# MCU.net
KiCad netlist of a schematic drawn in Altium Designer
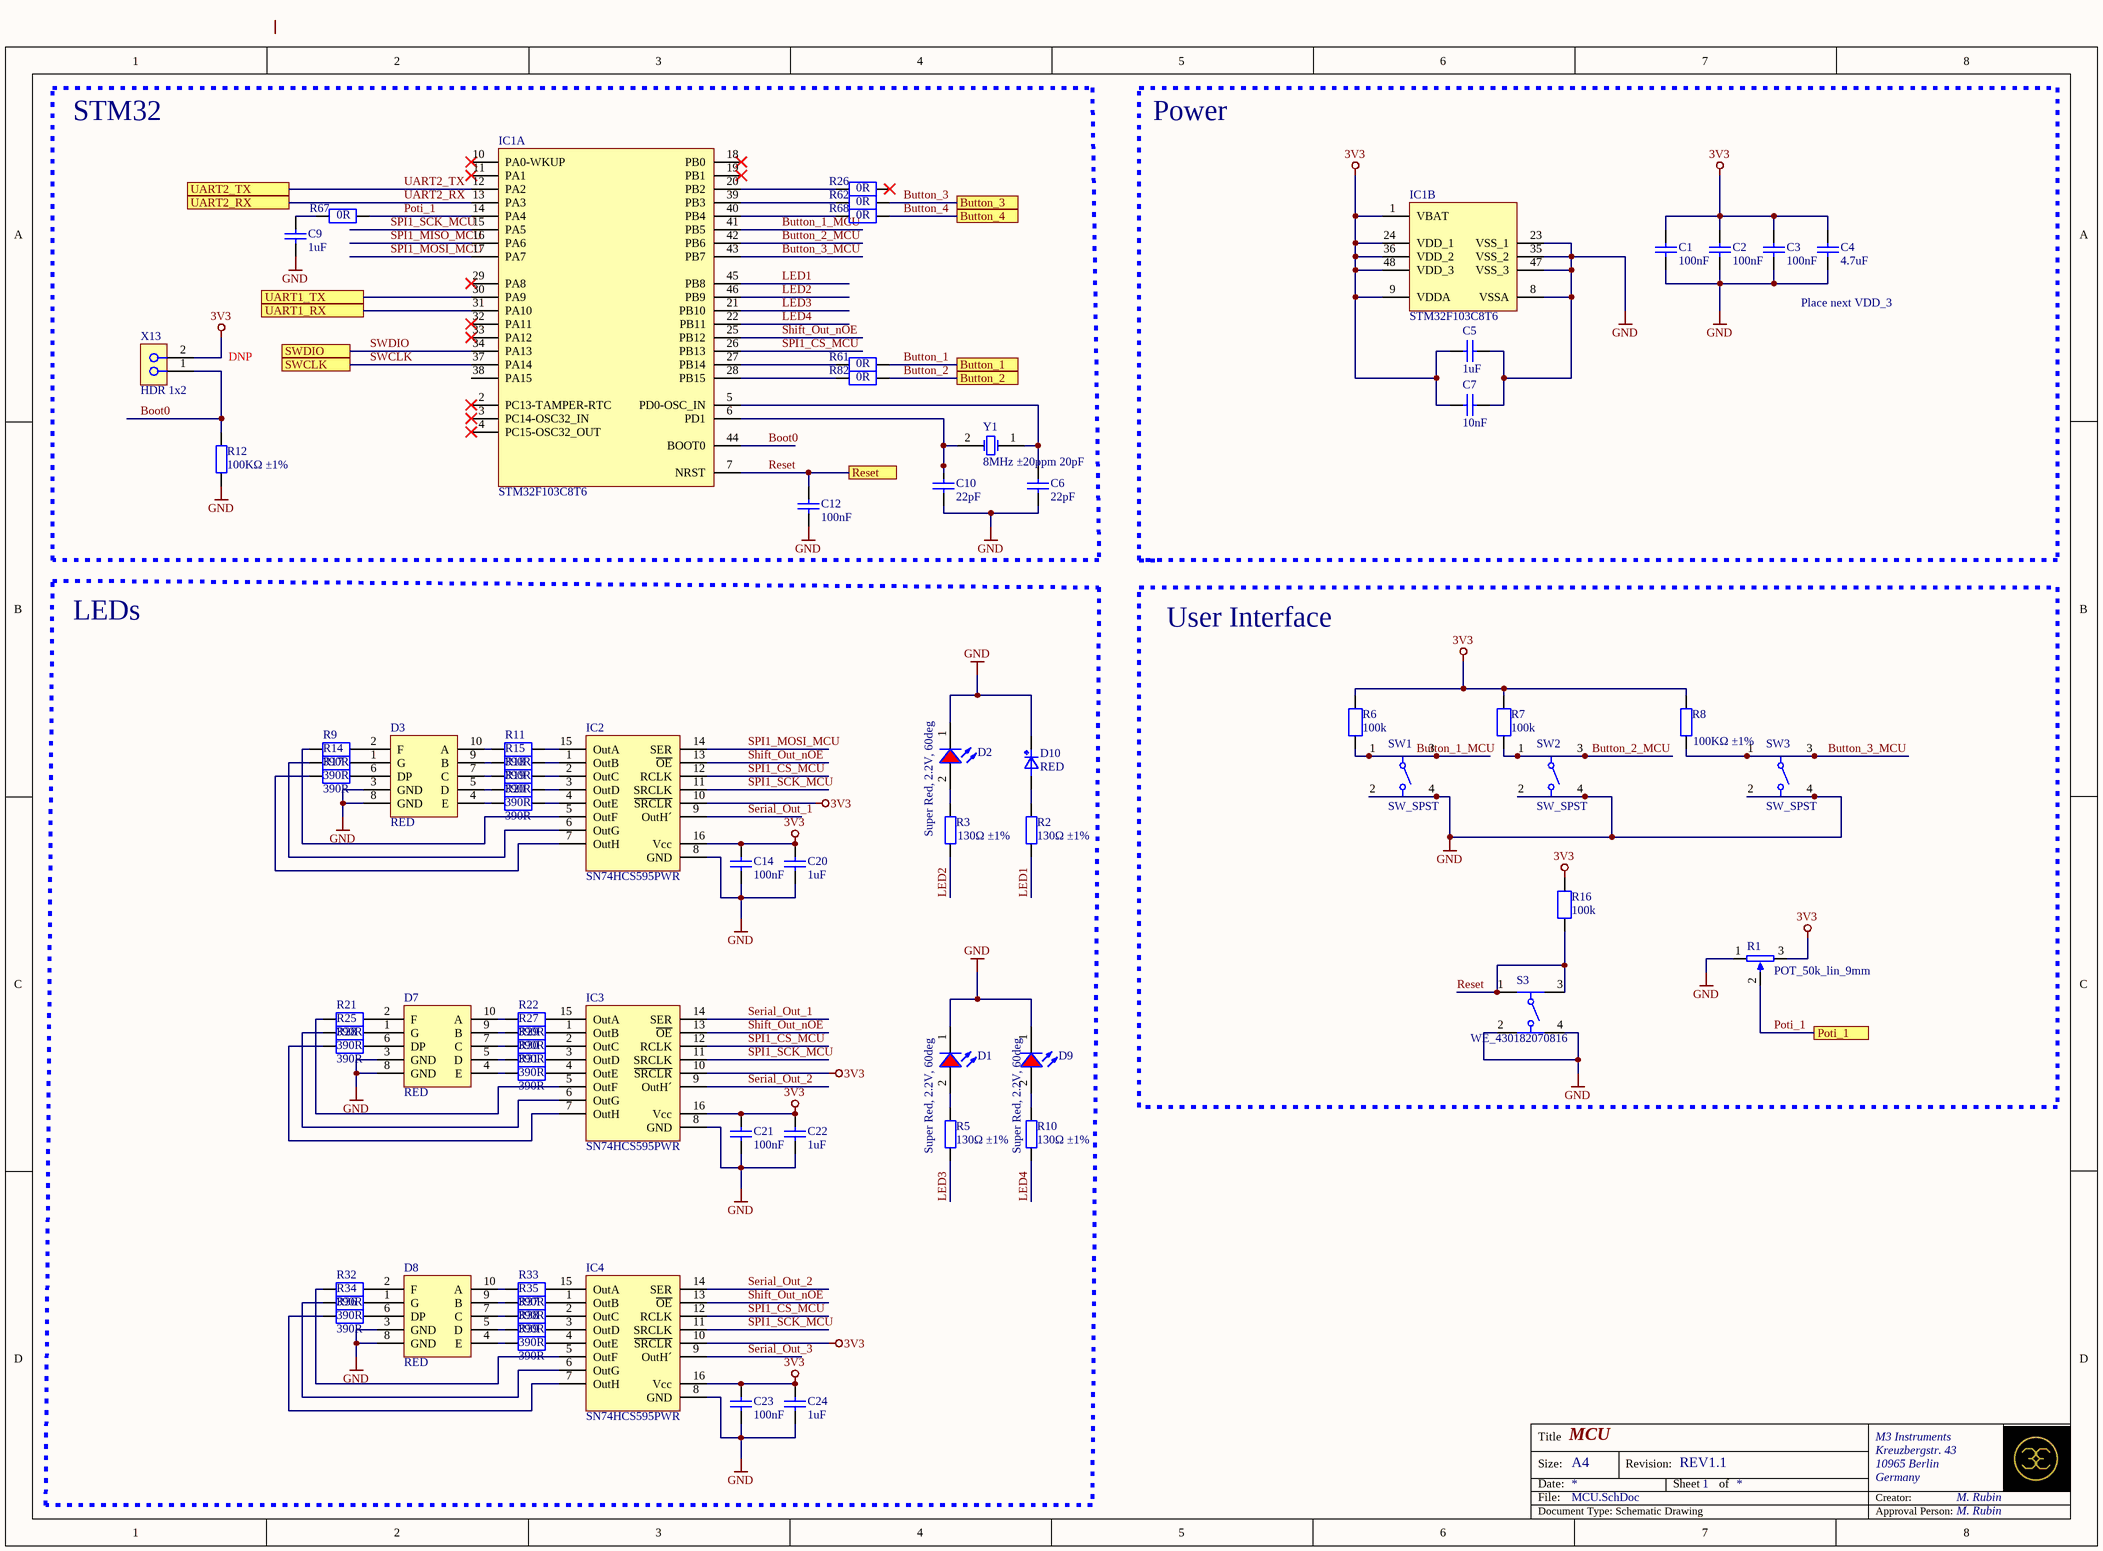
[diagram p0: MCU.SchDoc]

(export (version "E")
  (design (tool "Eeschema 10.0.6"))
  (components
    (comp (ref "C1")
      (value "100nF")
      (footprint "0603_C")
      (description "Chip capacitors")
      (fields (field (name "MANUFACTURER") "YAGEO") (field (name "PARTNUMBER") "CC0603KRX7R9BB104"))
      (libsource (lib "Cap") (part "0603 100nF (104) 10% 50V"))
    )
    (comp (ref "C2")
      (value "100nF")
      (footprint "0603_C")
      (description "Chip capacitors")
      (fields (field (name "MANUFACTURER") "YAGEO") (field (name "PARTNUMBER") "CC0603KRX7R9BB104"))
      (libsource (lib "Cap") (part "0603 100nF (104) 10% 50V"))
    )
    (comp (ref "C3")
      (value "100nF")
      (footprint "0603_C")
      (description "Chip capacitors")
      (fields (field (name "MANUFACTURER") "YAGEO") (field (name "PARTNUMBER") "CC0603KRX7R9BB104"))
      (libsource (lib "Cap") (part "0603 100nF (104) 10% 50V"))
    )
    (comp (ref "C4")
      (value "4.7uF")
      (footprint "0603_C")
      (description "Chip capacitors")
      (fields
        (field (name "MANUFACTURER") "Samsung Electro-Mechanics")
        (field (name "PARTNUMBER") "CL10A475KO8NNNC")
      )
      (libsource (lib "Cap") (part "0603 4.7uF (475) 10% 16V"))
    )
    (comp (ref "C5")
      (value "1uF")
      (footprint "0603_C")
      (description "Chip capacitors")
      (fields
        (field (name "MANUFACTURER") "Samsung Electro-Mechanics")
        (field (name "PARTNUMBER") "CL10A105KB8NNNC")
      )
      (libsource (lib "Cap") (part "0603 1uF (105) 10% 50V"))
    )
    (comp (ref "C6")
      (value "22pF")
      (footprint "0603_C")
      (description "Chip capacitors")
      (fields
        (field (name "MANUFACTURER") "Samsung Electro-Mechanics")
        (field (name "PARTNUMBER") "CL10C220JB8NNNC")
      )
      (libsource (lib "Cap") (part "0603 22pF (220) 5% 50V"))
    )
    (comp (ref "C7")
      (value "10nF")
      (footprint "0603_C")
      (description "Chip capacitors")
      (fields
        (field (name "MANUFACTURER") "Guangdong Fenghua Advanced Tech")
        (field (name "PARTNUMBER") "0603B103K500NT")
      )
      (libsource (lib "Cap") (part "0603 10nF (103) 10% 50V"))
    )
    (comp (ref "C9")
      (value "1uF")
      (footprint "0603_C")
      (description "Chip capacitors")
      (fields
        (field (name "MANUFACTURER") "Samsung Electro-Mechanics")
        (field (name "PARTNUMBER") "CL10A105KB8NNNC")
      )
      (libsource (lib "Cap") (part "0603 1uF (105) 10% 50V"))
    )
    (comp (ref "C10")
      (value "22pF")
      (footprint "0603_C")
      (description "Chip capacitors")
      (fields
        (field (name "MANUFACTURER") "Samsung Electro-Mechanics")
        (field (name "PARTNUMBER") "CL10C220JB8NNNC")
      )
      (libsource (lib "Cap") (part "0603 22pF (220) 5% 50V"))
    )
    (comp (ref "C12")
      (value "100nF")
      (footprint "0603_C")
      (description "Chip capacitors")
      (fields (field (name "MANUFACTURER") "YAGEO") (field (name "PARTNUMBER") "CC0603KRX7R9BB104"))
      (libsource (lib "Cap") (part "0603 100nF (104) 10% 50V"))
    )
    (comp (ref "C14")
      (value "100nF")
      (footprint "0603_C")
      (description "Chip capacitors")
      (fields (field (name "MANUFACTURER") "YAGEO") (field (name "PARTNUMBER") "CC0603KRX7R9BB104"))
      (libsource (lib "Cap") (part "0603 100nF (104) 10% 50V"))
    )
    (comp (ref "C20")
      (value "1uF")
      (footprint "0603_C")
      (description "Chip capacitors")
      (fields
        (field (name "MANUFACTURER") "Samsung Electro-Mechanics")
        (field (name "PARTNUMBER") "CL10A105KB8NNNC")
      )
      (libsource (lib "Cap") (part "0603 1uF (105) 10% 50V"))
    )
    (comp (ref "C21")
      (value "100nF")
      (footprint "0603_C")
      (description "Chip capacitors")
      (fields (field (name "MANUFACTURER") "YAGEO") (field (name "PARTNUMBER") "CC0603KRX7R9BB104"))
      (libsource (lib "Cap") (part "0603 100nF (104) 10% 50V"))
    )
    (comp (ref "C22")
      (value "1uF")
      (footprint "0603_C")
      (description "Chip capacitors")
      (fields
        (field (name "MANUFACTURER") "Samsung Electro-Mechanics")
        (field (name "PARTNUMBER") "CL10A105KB8NNNC")
      )
      (libsource (lib "Cap") (part "0603 1uF (105) 10% 50V"))
    )
    (comp (ref "C23")
      (value "100nF")
      (footprint "0603_C")
      (description "Chip capacitors")
      (fields (field (name "MANUFACTURER") "YAGEO") (field (name "PARTNUMBER") "CC0603KRX7R9BB104"))
      (libsource (lib "Cap") (part "0603 100nF (104) 10% 50V"))
    )
    (comp (ref "C24")
      (value "1uF")
      (footprint "0603_C")
      (description "Chip capacitors")
      (fields
        (field (name "MANUFACTURER") "Samsung Electro-Mechanics")
        (field (name "PARTNUMBER") "CL10A105KB8NNNC")
      )
      (libsource (lib "Cap") (part "0603 1uF (105) 10% 50V"))
    )
    (comp (ref "D1")
      (value "Super Red, 2.2V, 60deg")
      (footprint "WL-TMRC_3mm_10mm_space")
      (description "WL-TMRC THT Mono-color Round Color, size 3mm, Super Red, 2.2V, 60deg")
      (fields (field (name "PART NUMBER") "151031SS06000") (field (name "PUBLISHER") "Wurth Elektronik"))
      (libsource (lib "Diodes") (part "151031SS06000_Spacer_10mm"))
    )
    (comp (ref "D2")
      (value "Super Red, 2.2V, 60deg")
      (footprint "WL-TMRC_3mm_10mm_space")
      (description "WL-TMRC THT Mono-color Round Color, size 3mm, Super Red, 2.2V, 60deg")
      (fields (field (name "PART NUMBER") "151031SS06000") (field (name "PUBLISHER") "Wurth Elektronik"))
      (libsource (lib "Diodes") (part "151031SS06000_Spacer_10mm"))
    )
    (comp (ref "D3")
      (value "RED")
      (footprint "LTS-4301WC")
      (description "LED Displays & Accessories 1-Digit SMD Display Red Low-Cur .40")
      (fields (field (name "MANUFACTURER") "Lite-On") (field (name "MANUFACTURER PART NUMBER") "LTS-4301WC"))
      (libsource (lib "Diodes") (part "7-SEGMENT-10mm"))
    )
    (comp (ref "D7")
      (value "RED")
      (footprint "LTS-4301WC")
      (description "LED Displays & Accessories 1-Digit SMD Display Red Low-Cur .40")
      (fields (field (name "MANUFACTURER") "Lite-On") (field (name "MANUFACTURER PART NUMBER") "LTS-4301WC"))
      (libsource (lib "Diodes") (part "7-SEGMENT-10mm"))
    )
    (comp (ref "D8")
      (value "RED")
      (footprint "LTS-4301WC")
      (description "LED Displays & Accessories 1-Digit SMD Display Red Low-Cur .40")
      (fields (field (name "MANUFACTURER") "Lite-On") (field (name "MANUFACTURER PART NUMBER") "LTS-4301WC"))
      (libsource (lib "Diodes") (part "7-SEGMENT-10mm"))
    )
    (comp (ref "D9")
      (value "Super Red, 2.2V, 60deg")
      (footprint "WL-TMRC_3mm_10mm_space")
      (description "WL-TMRC THT Mono-color Round Color, size 3mm, Super Red, 2.2V, 60deg")
      (fields (field (name "PART NUMBER") "151031SS06000") (field (name "PUBLISHER") "Wurth Elektronik"))
      (libsource (lib "Diodes") (part "151031SS06000_Spacer_10mm"))
    )
    (comp (ref "D10")
      (value "RED")
      (footprint "WL-SMCW_0805")
      (description "Standard LEDs - SMD WL-SMCW SMDMono TpVw Waterclr 0805 Red")
      (fields
        (field (name "MANUFACTURER") "Wurth Elektronik")
        (field (name "MANUFACTURER PART NUMBER") "150080RS75000")
      )
      (libsource (lib "Diodes") (part "LED_0805_RED_AK"))
    )
    (comp (ref "IC1")
      (value "STM32F103C8T6")
      (footprint "LQFP-48_7x7x05P")
      (description "ARM")
      (fields (field (name "MANUFACTURER") "STMicroelectronics"))
      (libsource (lib "ICs") (part "STM32F103C8T6"))
    )
    (comp (ref "IC2")
      (value "SN74HCS595PWR")
      (footprint "TSOP65P640X120-16N_2")
      (description "Counter Shift Registers 8-bit serial-in/parallel-out shift register 16-TSSOP -40 to 125")
      (fields (field (name "MANUFACTURER") "Texas Instruments"))
      (libsource (lib "ICs") (part "IC_SN74HCS595"))
    )
    (comp (ref "IC3")
      (value "SN74HCS595PWR")
      (footprint "TSOP65P640X120-16N_2")
      (description "Counter Shift Registers 8-bit serial-in/parallel-out shift register 16-TSSOP -40 to 125")
      (fields (field (name "MANUFACTURER") "Texas Instruments"))
      (libsource (lib "ICs") (part "IC_SN74HCS595"))
    )
    (comp (ref "IC4")
      (value "SN74HCS595PWR")
      (footprint "TSOP65P640X120-16N_2")
      (description "Counter Shift Registers 8-bit serial-in/parallel-out shift register 16-TSSOP -40 to 125")
      (fields (field (name "MANUFACTURER") "Texas Instruments"))
      (libsource (lib "ICs") (part "IC_SN74HCS595"))
    )
    (comp (ref "R1")
      (value "POT_50k_lin_9mm")
      (footprint "PTV09")
      (description "Potentiometers PANEL CONTROL - 9MM-ST-CA 50 kohms 30 mm")
      (fields
        (field (name "MANUFACTURER") "Bourns")
        (field (name "MANUFACTURER PART NUMBER") "PTV09A-4030S-A503")
      )
      (libsource (lib "Resistors") (part "POT_50k_lin_9mm"))
    )
    (comp (ref "R2")
      (value "130Ω ±1%")
      (footprint "0603_R")
      (description "Chip resistor")
      (fields (field (name "MANUFACTURER") "Uniroyal Elec") (field (name "PARTNUMBER") "0603WAF1300T5E"))
      (libsource (lib "RES") (part "0603 130R (1300) 1%"))
    )
    (comp (ref "R3")
      (value "130Ω ±1%")
      (footprint "0603_R")
      (description "Chip resistor")
      (fields (field (name "MANUFACTURER") "Uniroyal Elec") (field (name "PARTNUMBER") "0603WAF1300T5E"))
      (libsource (lib "RES") (part "0603 130R (1300) 1%"))
    )
    (comp (ref "R5")
      (value "130Ω ±1%")
      (footprint "0603_R")
      (description "Chip resistor")
      (fields (field (name "MANUFACTURER") "Uniroyal Elec") (field (name "PARTNUMBER") "0603WAF1300T5E"))
      (libsource (lib "RES") (part "0603 130R (1300) 1%"))
    )
    (comp (ref "R6")
      (value "100k")
      (footprint "RESC2012X70N")
      (description "Thick Film Resistors - SMD 1/8watt 100Kohms 1% 100ppm")
      (fields
        (field (name "MANUFACTURER") "Vishay / Dale")
        (field (name "MANUFACTURER PART NUMBER") "CRCW0805100KFKEA")
      )
      (libsource (lib "Resistors") (part "RES_100k_0805"))
    )
    (comp (ref "R7")
      (value "100k")
      (footprint "RESC2012X70N")
      (description "Thick Film Resistors - SMD 1/8watt 100Kohms 1% 100ppm")
      (fields
        (field (name "MANUFACTURER") "Vishay / Dale")
        (field (name "MANUFACTURER PART NUMBER") "CRCW0805100KFKEA")
      )
      (libsource (lib "Resistors") (part "RES_100k_0805"))
    )
    (comp (ref "R8")
      (value "100KΩ ±1%")
      (footprint "0603_R")
      (description "Chip resistor")
      (fields (field (name "MANUFACTURER") "Uniroyal Elec") (field (name "PARTNUMBER") "0603WAF1003T5E"))
      (libsource (lib "RES") (part "0603 100K (1003) 1%"))
    )
    (comp (ref "R9")
      (value "390R")
      (footprint "RESC2012X70N")
      (description "Thick Film Resistors - SMD 1/8Watt 390ohms 1% Commercial Use")
      (fields
        (field (name "MANUFACTURER") "Vishay / Dale")
        (field (name "MANUFACTURER PART NUMBER") "CRCW0805390RFKEA")
      )
      (libsource (lib "Resistors") (part "RES_390R_0805"))
    )
    (comp (ref "R10")
      (value "130Ω ±1%")
      (footprint "0603_R")
      (description "Chip resistor")
      (fields (field (name "MANUFACTURER") "Uniroyal Elec") (field (name "PARTNUMBER") "0603WAF1300T5E"))
      (libsource (lib "RES") (part "0603 130R (1300) 1%"))
    )
    (comp (ref "R11")
      (value "390R")
      (footprint "RESC2012X70N")
      (description "Thick Film Resistors - SMD 1/8Watt 390ohms 1% Commercial Use")
      (fields
        (field (name "MANUFACTURER") "Vishay / Dale")
        (field (name "MANUFACTURER PART NUMBER") "CRCW0805390RFKEA")
      )
      (libsource (lib "Resistors") (part "RES_390R_0805"))
    )
    (comp (ref "R12")
      (value "100KΩ ±1%")
      (footprint "0603_R")
      (description "Chip resistor")
      (fields (field (name "MANUFACTURER") "Uniroyal Elec") (field (name "PARTNUMBER") "0603WAF1003T5E"))
      (libsource (lib "RES") (part "0603 100K (1003) 1%"))
    )
    (comp (ref "R14")
      (value "390R")
      (footprint "RESC2012X70N")
      (description "Thick Film Resistors - SMD 1/8Watt 390ohms 1% Commercial Use")
      (fields
        (field (name "MANUFACTURER") "Vishay / Dale")
        (field (name "MANUFACTURER PART NUMBER") "CRCW0805390RFKEA")
      )
      (libsource (lib "Resistors") (part "RES_390R_0805"))
    )
    (comp (ref "R15")
      (value "390R")
      (footprint "RESC2012X70N")
      (description "Thick Film Resistors - SMD 1/8Watt 390ohms 1% Commercial Use")
      (fields
        (field (name "MANUFACTURER") "Vishay / Dale")
        (field (name "MANUFACTURER PART NUMBER") "CRCW0805390RFKEA")
      )
      (libsource (lib "Resistors") (part "RES_390R_0805"))
    )
    (comp (ref "R16")
      (value "100k")
      (footprint "RESC2012X70N")
      (description "Thick Film Resistors - SMD 1/8watt 100Kohms 1% 100ppm")
      (fields
        (field (name "MANUFACTURER") "Vishay / Dale")
        (field (name "MANUFACTURER PART NUMBER") "CRCW0805100KFKEA")
      )
      (libsource (lib "Resistors") (part "RES_100k_0805"))
    )
    (comp (ref "R17")
      (value "390R")
      (footprint "RESC2012X70N")
      (description "Thick Film Resistors - SMD 1/8Watt 390ohms 1% Commercial Use")
      (fields
        (field (name "MANUFACTURER") "Vishay / Dale")
        (field (name "MANUFACTURER PART NUMBER") "CRCW0805390RFKEA")
      )
      (libsource (lib "Resistors") (part "RES_390R_0805"))
    )
    (comp (ref "R18")
      (value "390R")
      (footprint "RESC2012X70N")
      (description "Thick Film Resistors - SMD 1/8Watt 390ohms 1% Commercial Use")
      (fields
        (field (name "MANUFACTURER") "Vishay / Dale")
        (field (name "MANUFACTURER PART NUMBER") "CRCW0805390RFKEA")
      )
      (libsource (lib "Resistors") (part "RES_390R_0805"))
    )
    (comp (ref "R19")
      (value "390R")
      (footprint "RESC2012X70N")
      (description "Thick Film Resistors - SMD 1/8Watt 390ohms 1% Commercial Use")
      (fields
        (field (name "MANUFACTURER") "Vishay / Dale")
        (field (name "MANUFACTURER PART NUMBER") "CRCW0805390RFKEA")
      )
      (libsource (lib "Resistors") (part "RES_390R_0805"))
    )
    (comp (ref "R20")
      (value "390R")
      (footprint "RESC2012X70N")
      (description "Thick Film Resistors - SMD 1/8Watt 390ohms 1% Commercial Use")
      (fields
        (field (name "MANUFACTURER") "Vishay / Dale")
        (field (name "MANUFACTURER PART NUMBER") "CRCW0805390RFKEA")
      )
      (libsource (lib "Resistors") (part "RES_390R_0805"))
    )
    (comp (ref "R21")
      (value "390R")
      (footprint "RESC2012X70N")
      (description "Thick Film Resistors - SMD 1/8Watt 390ohms 1% Commercial Use")
      (fields
        (field (name "MANUFACTURER") "Vishay / Dale")
        (field (name "MANUFACTURER PART NUMBER") "CRCW0805390RFKEA")
      )
      (libsource (lib "Resistors") (part "RES_390R_0805"))
    )
    (comp (ref "R22")
      (value "390R")
      (footprint "RESC2012X70N")
      (description "Thick Film Resistors - SMD 1/8Watt 390ohms 1% Commercial Use")
      (fields
        (field (name "MANUFACTURER") "Vishay / Dale")
        (field (name "MANUFACTURER PART NUMBER") "CRCW0805390RFKEA")
      )
      (libsource (lib "Resistors") (part "RES_390R_0805"))
    )
    (comp (ref "R25")
      (value "390R")
      (footprint "RESC2012X70N")
      (description "Thick Film Resistors - SMD 1/8Watt 390ohms 1% Commercial Use")
      (fields
        (field (name "MANUFACTURER") "Vishay / Dale")
        (field (name "MANUFACTURER PART NUMBER") "CRCW0805390RFKEA")
      )
      (libsource (lib "Resistors") (part "RES_390R_0805"))
    )
    (comp (ref "R26")
      (value "0R")
      (footprint "RESC1608X55N")
      (description "Thick Film Resistors - SMD 1/10watt ZEROohm Jumper")
      (fields
        (field (name "MANUFACTURER") "Vishay")
        (field (name "MANUFACTURER PART NUMBER") "CRCW06030000Z0EA")
      )
      (libsource (lib "Resistors") (part "RES_0R_0603"))
    )
    (comp (ref "R27")
      (value "390R")
      (footprint "RESC2012X70N")
      (description "Thick Film Resistors - SMD 1/8Watt 390ohms 1% Commercial Use")
      (fields
        (field (name "MANUFACTURER") "Vishay / Dale")
        (field (name "MANUFACTURER PART NUMBER") "CRCW0805390RFKEA")
      )
      (libsource (lib "Resistors") (part "RES_390R_0805"))
    )
    (comp (ref "R28")
      (value "390R")
      (footprint "RESC2012X70N")
      (description "Thick Film Resistors - SMD 1/8Watt 390ohms 1% Commercial Use")
      (fields
        (field (name "MANUFACTURER") "Vishay / Dale")
        (field (name "MANUFACTURER PART NUMBER") "CRCW0805390RFKEA")
      )
      (libsource (lib "Resistors") (part "RES_390R_0805"))
    )
    (comp (ref "R29")
      (value "390R")
      (footprint "RESC2012X70N")
      (description "Thick Film Resistors - SMD 1/8Watt 390ohms 1% Commercial Use")
      (fields
        (field (name "MANUFACTURER") "Vishay / Dale")
        (field (name "MANUFACTURER PART NUMBER") "CRCW0805390RFKEA")
      )
      (libsource (lib "Resistors") (part "RES_390R_0805"))
    )
    (comp (ref "R30")
      (value "390R")
      (footprint "RESC2012X70N")
      (description "Thick Film Resistors - SMD 1/8Watt 390ohms 1% Commercial Use")
      (fields
        (field (name "MANUFACTURER") "Vishay / Dale")
        (field (name "MANUFACTURER PART NUMBER") "CRCW0805390RFKEA")
      )
      (libsource (lib "Resistors") (part "RES_390R_0805"))
    )
    (comp (ref "R31")
      (value "390R")
      (footprint "RESC2012X70N")
      (description "Thick Film Resistors - SMD 1/8Watt 390ohms 1% Commercial Use")
      (fields
        (field (name "MANUFACTURER") "Vishay / Dale")
        (field (name "MANUFACTURER PART NUMBER") "CRCW0805390RFKEA")
      )
      (libsource (lib "Resistors") (part "RES_390R_0805"))
    )
    (comp (ref "R32")
      (value "390R")
      (footprint "RESC2012X70N")
      (description "Thick Film Resistors - SMD 1/8Watt 390ohms 1% Commercial Use")
      (fields
        (field (name "MANUFACTURER") "Vishay / Dale")
        (field (name "MANUFACTURER PART NUMBER") "CRCW0805390RFKEA")
      )
      (libsource (lib "Resistors") (part "RES_390R_0805"))
    )
    (comp (ref "R33")
      (value "390R")
      (footprint "RESC2012X70N")
      (description "Thick Film Resistors - SMD 1/8Watt 390ohms 1% Commercial Use")
      (fields
        (field (name "MANUFACTURER") "Vishay / Dale")
        (field (name "MANUFACTURER PART NUMBER") "CRCW0805390RFKEA")
      )
      (libsource (lib "Resistors") (part "RES_390R_0805"))
    )
    (comp (ref "R34")
      (value "390R")
      (footprint "RESC2012X70N")
      (description "Thick Film Resistors - SMD 1/8Watt 390ohms 1% Commercial Use")
      (fields
        (field (name "MANUFACTURER") "Vishay / Dale")
        (field (name "MANUFACTURER PART NUMBER") "CRCW0805390RFKEA")
      )
      (libsource (lib "Resistors") (part "RES_390R_0805"))
    )
    (comp (ref "R35")
      (value "390R")
      (footprint "RESC2012X70N")
      (description "Thick Film Resistors - SMD 1/8Watt 390ohms 1% Commercial Use")
      (fields
        (field (name "MANUFACTURER") "Vishay / Dale")
        (field (name "MANUFACTURER PART NUMBER") "CRCW0805390RFKEA")
      )
      (libsource (lib "Resistors") (part "RES_390R_0805"))
    )
    (comp (ref "R36")
      (value "390R")
      (footprint "RESC2012X70N")
      (description "Thick Film Resistors - SMD 1/8Watt 390ohms 1% Commercial Use")
      (fields
        (field (name "MANUFACTURER") "Vishay / Dale")
        (field (name "MANUFACTURER PART NUMBER") "CRCW0805390RFKEA")
      )
      (libsource (lib "Resistors") (part "RES_390R_0805"))
    )
    (comp (ref "R37")
      (value "390R")
      (footprint "RESC2012X70N")
      (description "Thick Film Resistors - SMD 1/8Watt 390ohms 1% Commercial Use")
      (fields
        (field (name "MANUFACTURER") "Vishay / Dale")
        (field (name "MANUFACTURER PART NUMBER") "CRCW0805390RFKEA")
      )
      (libsource (lib "Resistors") (part "RES_390R_0805"))
    )
    (comp (ref "R38")
      (value "390R")
      (footprint "RESC2012X70N")
      (description "Thick Film Resistors - SMD 1/8Watt 390ohms 1% Commercial Use")
      (fields
        (field (name "MANUFACTURER") "Vishay / Dale")
        (field (name "MANUFACTURER PART NUMBER") "CRCW0805390RFKEA")
      )
      (libsource (lib "Resistors") (part "RES_390R_0805"))
    )
    (comp (ref "R39")
      (value "390R")
      (footprint "RESC2012X70N")
      (description "Thick Film Resistors - SMD 1/8Watt 390ohms 1% Commercial Use")
      (fields
        (field (name "MANUFACTURER") "Vishay / Dale")
        (field (name "MANUFACTURER PART NUMBER") "CRCW0805390RFKEA")
      )
      (libsource (lib "Resistors") (part "RES_390R_0805"))
    )
    (comp (ref "R61")
      (value "0R")
      (footprint "RESC1608X55N")
      (description "Thick Film Resistors - SMD 1/10watt ZEROohm Jumper")
      (fields
        (field (name "MANUFACTURER") "Vishay")
        (field (name "MANUFACTURER PART NUMBER") "CRCW06030000Z0EA")
      )
      (libsource (lib "Resistors") (part "RES_0R_0603"))
    )
    (comp (ref "R62")
      (value "0R")
      (footprint "RESC1608X55N")
      (description "Thick Film Resistors - SMD 1/10watt ZEROohm Jumper")
      (fields
        (field (name "MANUFACTURER") "Vishay")
        (field (name "MANUFACTURER PART NUMBER") "CRCW06030000Z0EA")
      )
      (libsource (lib "Resistors") (part "RES_0R_0603"))
    )
    (comp (ref "R67")
      (value "0R")
      (footprint "RESC1608X55N")
      (description "Thick Film Resistors - SMD 1/10watt ZEROohm Jumper")
      (fields
        (field (name "MANUFACTURER") "Vishay")
        (field (name "MANUFACTURER PART NUMBER") "CRCW06030000Z0EA")
      )
      (libsource (lib "Resistors") (part "RES_0R_0603"))
    )
    (comp (ref "R68")
      (value "0R")
      (footprint "RESC1608X55N")
      (description "Thick Film Resistors - SMD 1/10watt ZEROohm Jumper")
      (fields
        (field (name "MANUFACTURER") "Vishay")
        (field (name "MANUFACTURER PART NUMBER") "CRCW06030000Z0EA")
      )
      (libsource (lib "Resistors") (part "RES_0R_0603"))
    )
    (comp (ref "R82")
      (value "0R")
      (footprint "RESC1608X55N")
      (description "Thick Film Resistors - SMD 1/10watt ZEROohm Jumper")
      (fields
        (field (name "MANUFACTURER") "Vishay")
        (field (name "MANUFACTURER PART NUMBER") "CRCW06030000Z0EA")
      )
      (libsource (lib "Resistors") (part "RES_0R_0603"))
    )
    (comp (ref "S3")
      (value "WE_430182070816")
      (footprint "430182070816")
      (description "WS-TASV SMT Tact Switch 6x6mm, height 7mm, 160gf")
      (fields (field (name "PART NUMBER") "430182070816") (field (name "PUBLISHER") "Wurth Elektronik"))
      (libsource (lib "Switches") (part "WE_430182070816"))
    )
    (comp (ref "SW1")
      (value "SW_SPST")
      (footprint "TL1105D")
      (description "Tastschalter SPST-Schließer Von oben betätigt Durchkontaktierung")
      (fields
        (field (name "MANUFACTURER") "E-Switch")
        (field (name "MANUFACTURER PART NUMBER") "TL1105DF160Q")
      )
      (libsource (lib "Switches") (part "SW_ TL1105DF160Q"))
    )
    (comp (ref "SW2")
      (value "SW_SPST")
      (footprint "TL1105D")
      (description "Tastschalter SPST-Schließer Von oben betätigt Durchkontaktierung")
      (fields
        (field (name "MANUFACTURER") "E-Switch")
        (field (name "MANUFACTURER PART NUMBER") "TL1105DF160Q")
      )
      (libsource (lib "Switches") (part "SW_ TL1105DF160Q"))
    )
    (comp (ref "SW3")
      (value "SW_SPST")
      (footprint "TL1105D")
      (description "Tastschalter SPST-Schließer Von oben betätigt Durchkontaktierung")
      (fields
        (field (name "MANUFACTURER") "E-Switch")
        (field (name "MANUFACTURER PART NUMBER") "TL1105DF160Q")
      )
      (libsource (lib "Switches") (part "SW_ TL1105DF160Q"))
    )
    (comp (ref "X13")
      (value "HDR 1x2")
      (footprint "CON_HEADER2.54_1x2W")
      (description "Board-to-Board-Steckverbinder, 2.54 mm, 2 Kontakt(e), Stiftleiste 1-Reihig")
      (fields
        (field (name "MANUFACTURER") "Samtec")
        (field (name "MANUFACTURER PART NUMBER") "TSW-102-07-T-S")
      )
      (libsource (lib "Connectors") (part "CON_HEADER_1X2"))
    )
    (comp (ref "Y1")
      (value "8MHz ±20ppm 20pF")
      (footprint "SMD-5032_2P")
      (description "贴片晶振")
      (libsource (lib "CrystalOscillator") (part "SMD-5032_2P 8MHz 20ppm 20pF"))
    )
  )
  (nets
    (net (code "1") (name "/Boot0") (class "Default")
      (node (ref "IC1") (pin "44") (pinfunction "BOOT0_44") (pintype "passive"))
      (node (ref "R12") (pin "2") (pinfunction "2_2") (pintype "passive"))
      (node (ref "X13") (pin "1") (pinfunction "1_1") (pintype "passive"))
    )
    (net (code "2") (name "/Button_1") (class "Default")
      (node (ref "R61") (pin "2") (pinfunction "2_2") (pintype "passive"))
    )
    (net (code "3") (name "/Button_1_MCU") (class "Default")
      (node (ref "IC1") (pin "41") (pinfunction "PB5_41") (pintype "passive"))
      (node (ref "R6") (pin "1") (pinfunction "1_1") (pintype "passive"))
      (node (ref "SW1") (pin "1") (pinfunction "1_1") (pintype "passive"))
      (node (ref "SW1") (pin "3") (pinfunction "3_3") (pintype "passive"))
    )
    (net (code "4") (name "/Button_2") (class "Default")
      (node (ref "R82") (pin "2") (pinfunction "2_2") (pintype "passive"))
    )
    (net (code "5") (name "/Button_2_MCU") (class "Default")
      (node (ref "IC1") (pin "42") (pinfunction "PB6_42") (pintype "passive"))
      (node (ref "R7") (pin "1") (pinfunction "1_1") (pintype "passive"))
      (node (ref "SW2") (pin "1") (pinfunction "1_1") (pintype "passive"))
      (node (ref "SW2") (pin "3") (pinfunction "3_3") (pintype "passive"))
    )
    (net (code "6") (name "/Button_3") (class "Default")
      (node (ref "R62") (pin "2") (pinfunction "2_2") (pintype "passive"))
    )
    (net (code "7") (name "/Button_3_MCU") (class "Default")
      (node (ref "IC1") (pin "43") (pinfunction "PB7_43") (pintype "passive"))
      (node (ref "R8") (pin "1") (pinfunction "1_1") (pintype "passive"))
      (node (ref "SW3") (pin "1") (pinfunction "1_1") (pintype "passive"))
      (node (ref "SW3") (pin "3") (pinfunction "3_3") (pintype "passive"))
    )
    (net (code "8") (name "/Button_4") (class "Default")
      (node (ref "R68") (pin "2") (pinfunction "2_2") (pintype "passive"))
    )
    (net (code "9") (name "/LED1") (class "Default")
      (node (ref "IC1") (pin "45") (pinfunction "PB8_45") (pintype "passive"))
      (node (ref "R2") (pin "2") (pinfunction "2_2") (pintype "passive"))
    )
    (net (code "10") (name "/LED2") (class "Default")
      (node (ref "IC1") (pin "46") (pinfunction "PB9_46") (pintype "passive"))
      (node (ref "R3") (pin "2") (pinfunction "2_2") (pintype "passive"))
    )
    (net (code "11") (name "/LED3") (class "Default")
      (node (ref "IC1") (pin "21") (pinfunction "PB10_21") (pintype "passive"))
      (node (ref "R5") (pin "2") (pinfunction "2_2") (pintype "passive"))
    )
    (net (code "12") (name "/LED4") (class "Default")
      (node (ref "IC1") (pin "22") (pinfunction "PB11_22") (pintype "passive"))
      (node (ref "R10") (pin "2") (pinfunction "2_2") (pintype "passive"))
    )
    (net (code "13") (name "/Poti_1") (class "Default")
      (node (ref "IC1") (pin "14") (pinfunction "PA4_14") (pintype "passive"))
      (node (ref "R1") (pin "2") (pinfunction "2_2") (pintype "passive"))
      (node (ref "R67") (pin "2") (pinfunction "2_2") (pintype "passive"))
    )
    (net (code "14") (name "/Reset") (class "Default")
      (node (ref "C12") (pin "2") (pinfunction "2_2") (pintype "passive"))
      (node (ref "IC1") (pin "7") (pinfunction "NRST_7") (pintype "passive"))
      (node (ref "R16") (pin "1") (pinfunction "1_1") (pintype "passive"))
      (node (ref "S3") (pin "1") (pinfunction "1_1") (pintype "passive"))
      (node (ref "S3") (pin "3") (pinfunction "3_3") (pintype "passive"))
    )
    (net (code "15") (name "/SPI1_CS_MCU") (class "Default")
      (node (ref "IC1") (pin "26") (pinfunction "PB13_26") (pintype "passive"))
      (node (ref "IC2") (pin "12") (pinfunction "RCLK_12") (pintype "passive"))
      (node (ref "IC3") (pin "12") (pinfunction "RCLK_12") (pintype "passive"))
      (node (ref "IC4") (pin "12") (pinfunction "RCLK_12") (pintype "passive"))
    )
    (net (code "16") (name "/SPI1_MISO_MCU") (class "Default")
      (node (ref "IC1") (pin "16") (pinfunction "PA6_16") (pintype "passive"))
    )
    (net (code "17") (name "/SPI1_MOSI_MCU") (class "Default")
      (node (ref "IC1") (pin "17") (pinfunction "PA7_17") (pintype "passive"))
      (node (ref "IC2") (pin "14") (pinfunction "SER_14") (pintype "passive"))
    )
    (net (code "18") (name "/SPI1_SCK_MCU") (class "Default")
      (node (ref "IC1") (pin "15") (pinfunction "PA5_15") (pintype "passive"))
      (node (ref "IC2") (pin "11") (pinfunction "SRCLK_11") (pintype "passive"))
      (node (ref "IC3") (pin "11") (pinfunction "SRCLK_11") (pintype "passive"))
      (node (ref "IC4") (pin "11") (pinfunction "SRCLK_11") (pintype "passive"))
    )
    (net (code "19") (name "/SWCLK") (class "Default")
      (node (ref "IC1") (pin "37") (pinfunction "PA14_37") (pintype "passive"))
    )
    (net (code "20") (name "/SWDIO") (class "Default")
      (node (ref "IC1") (pin "34") (pinfunction "PA13_34") (pintype "passive"))
    )
    (net (code "21") (name "/Serial_Out_1") (class "Default")
      (node (ref "IC2") (pin "9") (pinfunction "OutH´_9") (pintype "passive"))
      (node (ref "IC3") (pin "14") (pinfunction "SER_14") (pintype "passive"))
    )
    (net (code "22") (name "/Serial_Out_2") (class "Default")
      (node (ref "IC3") (pin "9") (pinfunction "OutH´_9") (pintype "passive"))
      (node (ref "IC4") (pin "14") (pinfunction "SER_14") (pintype "passive"))
    )
    (net (code "23") (name "/Serial_Out_3") (class "Default")
      (node (ref "IC4") (pin "9") (pinfunction "OutH´_9") (pintype "passive"))
    )
    (net (code "24") (name "/Shift_Out_nOE") (class "Default")
      (node (ref "IC1") (pin "25") (pinfunction "PB12_25") (pintype "passive"))
      (node (ref "IC2") (pin "13") (pinfunction "~{OE}_13") (pintype "passive"))
      (node (ref "IC3") (pin "13") (pinfunction "~{OE}_13") (pintype "passive"))
      (node (ref "IC4") (pin "13") (pinfunction "~{OE}_13") (pintype "passive"))
    )
    (net (code "25") (name "/UART1_RX") (class "Default")
      (node (ref "IC1") (pin "31") (pinfunction "PA10_31") (pintype "passive"))
    )
    (net (code "26") (name "/UART1_TX") (class "Default")
      (node (ref "IC1") (pin "30") (pinfunction "PA9_30") (pintype "passive"))
    )
    (net (code "27") (name "/UART2_RX") (class "Default")
      (node (ref "IC1") (pin "13") (pinfunction "PA3_13") (pintype "passive"))
    )
    (net (code "28") (name "/UART2_TX") (class "Default")
      (node (ref "IC1") (pin "12") (pinfunction "PA2_12") (pintype "passive"))
    )
    (net (code "29") (name "3V3") (class "Default")
      (node (ref "C1") (pin "2") (pinfunction "2_2") (pintype "passive"))
      (node (ref "C14") (pin "2") (pinfunction "2_2") (pintype "passive"))
      (node (ref "C2") (pin "2") (pinfunction "2_2") (pintype "passive"))
      (node (ref "C20") (pin "2") (pinfunction "2_2") (pintype "passive"))
      (node (ref "C21") (pin "2") (pinfunction "2_2") (pintype "passive"))
      (node (ref "C22") (pin "2") (pinfunction "2_2") (pintype "passive"))
      (node (ref "C23") (pin "2") (pinfunction "2_2") (pintype "passive"))
      (node (ref "C24") (pin "2") (pinfunction "2_2") (pintype "passive"))
      (node (ref "C3") (pin "2") (pinfunction "2_2") (pintype "passive"))
      (node (ref "C4") (pin "2") (pinfunction "2_2") (pintype "passive"))
      (node (ref "C5") (pin "1") (pinfunction "1_1") (pintype "passive"))
      (node (ref "C7") (pin "1") (pinfunction "1_1") (pintype "passive"))
      (node (ref "IC1") (pin "1") (pinfunction "VBAT_1") (pintype "power_in"))
      (node (ref "IC1") (pin "24") (pinfunction "VDD_1_24") (pintype "power_in"))
      (node (ref "IC1") (pin "36") (pinfunction "VDD_2_36") (pintype "power_in"))
      (node (ref "IC1") (pin "48") (pinfunction "VDD_3_48") (pintype "power_in"))
      (node (ref "IC1") (pin "9") (pinfunction "VDDA_9") (pintype "power_in"))
      (node (ref "IC2") (pin "10") (pinfunction "~{SRCLR}_10") (pintype "passive"))
      (node (ref "IC2") (pin "16") (pinfunction "Vcc_16") (pintype "passive"))
      (node (ref "IC3") (pin "10") (pinfunction "~{SRCLR}_10") (pintype "passive"))
      (node (ref "IC3") (pin "16") (pinfunction "Vcc_16") (pintype "passive"))
      (node (ref "IC4") (pin "10") (pinfunction "~{SRCLR}_10") (pintype "passive"))
      (node (ref "IC4") (pin "16") (pinfunction "Vcc_16") (pintype "passive"))
      (node (ref "R1") (pin "3") (pinfunction "3_3") (pintype "passive"))
      (node (ref "R16") (pin "2") (pinfunction "2_2") (pintype "passive"))
      (node (ref "R6") (pin "2") (pinfunction "2_2") (pintype "passive"))
      (node (ref "R7") (pin "2") (pinfunction "2_2") (pintype "passive"))
      (node (ref "R8") (pin "2") (pinfunction "2_2") (pintype "passive"))
      (node (ref "X13") (pin "2") (pinfunction "2_2") (pintype "passive"))
    )
    (net (code "30") (name "GND") (class "Default")
      (node (ref "C1") (pin "1") (pinfunction "1_1") (pintype "passive"))
      (node (ref "C10") (pin "2") (pinfunction "2_2") (pintype "passive"))
      (node (ref "C12") (pin "1") (pinfunction "1_1") (pintype "passive"))
      (node (ref "C14") (pin "1") (pinfunction "1_1") (pintype "passive"))
      (node (ref "C2") (pin "1") (pinfunction "1_1") (pintype "passive"))
      (node (ref "C20") (pin "1") (pinfunction "1_1") (pintype "passive"))
      (node (ref "C21") (pin "1") (pinfunction "1_1") (pintype "passive"))
      (node (ref "C22") (pin "1") (pinfunction "1_1") (pintype "passive"))
      (node (ref "C23") (pin "1") (pinfunction "1_1") (pintype "passive"))
      (node (ref "C24") (pin "1") (pinfunction "1_1") (pintype "passive"))
      (node (ref "C3") (pin "1") (pinfunction "1_1") (pintype "passive"))
      (node (ref "C4") (pin "1") (pinfunction "1_1") (pintype "passive"))
      (node (ref "C5") (pin "2") (pinfunction "2_2") (pintype "passive"))
      (node (ref "C6") (pin "2") (pinfunction "2_2") (pintype "passive"))
      (node (ref "C7") (pin "2") (pinfunction "2_2") (pintype "passive"))
      (node (ref "C9") (pin "2") (pinfunction "2_2") (pintype "passive"))
      (node (ref "D1") (pin "1") (pinfunction "K_1") (pintype "passive"))
      (node (ref "D10") (pin "K") (pinfunction "K_K") (pintype "passive"))
      (node (ref "D2") (pin "1") (pinfunction "K_1") (pintype "passive"))
      (node (ref "D3") (pin "3") (pinfunction "GND_3") (pintype "passive"))
      (node (ref "D3") (pin "8") (pinfunction "GND_8") (pintype "passive"))
      (node (ref "D7") (pin "3") (pinfunction "GND_3") (pintype "passive"))
      (node (ref "D7") (pin "8") (pinfunction "GND_8") (pintype "passive"))
      (node (ref "D8") (pin "3") (pinfunction "GND_3") (pintype "passive"))
      (node (ref "D8") (pin "8") (pinfunction "GND_8") (pintype "passive"))
      (node (ref "D9") (pin "1") (pinfunction "K_1") (pintype "passive"))
      (node (ref "IC1") (pin "23") (pinfunction "VSS_1_23") (pintype "power_in"))
      (node (ref "IC1") (pin "35") (pinfunction "VSS_2_35") (pintype "power_in"))
      (node (ref "IC1") (pin "47") (pinfunction "VSS_3_47") (pintype "power_in"))
      (node (ref "IC1") (pin "8") (pinfunction "VSSA_8") (pintype "power_in"))
      (node (ref "IC2") (pin "8") (pinfunction "GND_8") (pintype "passive"))
      (node (ref "IC3") (pin "8") (pinfunction "GND_8") (pintype "passive"))
      (node (ref "IC4") (pin "8") (pinfunction "GND_8") (pintype "passive"))
      (node (ref "R1") (pin "1") (pinfunction "1_1") (pintype "passive"))
      (node (ref "R12") (pin "1") (pinfunction "1_1") (pintype "passive"))
      (node (ref "S3") (pin "2") (pinfunction "2_2") (pintype "passive"))
      (node (ref "S3") (pin "4") (pinfunction "4_4") (pintype "passive"))
      (node (ref "SW1") (pin "2") (pinfunction "2_2") (pintype "passive"))
      (node (ref "SW1") (pin "4") (pinfunction "4_4") (pintype "passive"))
      (node (ref "SW2") (pin "2") (pinfunction "2_2") (pintype "passive"))
      (node (ref "SW2") (pin "4") (pinfunction "4_4") (pintype "passive"))
      (node (ref "SW3") (pin "2") (pinfunction "2_2") (pintype "passive"))
      (node (ref "SW3") (pin "4") (pinfunction "4_4") (pintype "passive"))
    )
    (net (code "31") (name "Net-(C9-Pad1)") (class "Default")
      (node (ref "C9") (pin "1") (pinfunction "1_1") (pintype "passive"))
      (node (ref "R67") (pin "1") (pinfunction "1_1") (pintype "passive"))
    )
    (net (code "32") (name "Net-(D1-A)") (class "Default")
      (node (ref "D1") (pin "2") (pinfunction "A_2") (pintype "passive"))
      (node (ref "R5") (pin "1") (pinfunction "1_1") (pintype "passive"))
    )
    (net (code "33") (name "Net-(D2-A)") (class "Default")
      (node (ref "D2") (pin "2") (pinfunction "A_2") (pintype "passive"))
      (node (ref "R3") (pin "1") (pinfunction "1_1") (pintype "passive"))
    )
    (net (code "34") (name "Net-(D3-A)") (class "Default")
      (node (ref "D3") (pin "10") (pinfunction "A_10") (pintype "passive"))
      (node (ref "R11") (pin "1") (pinfunction "1_1") (pintype "passive"))
    )
    (net (code "35") (name "Net-(D3-B)") (class "Default")
      (node (ref "D3") (pin "9") (pinfunction "B_9") (pintype "passive"))
      (node (ref "R15") (pin "1") (pinfunction "1_1") (pintype "passive"))
    )
    (net (code "36") (name "Net-(D3-C)") (class "Default")
      (node (ref "D3") (pin "7") (pinfunction "C_7") (pintype "passive"))
      (node (ref "R18") (pin "1") (pinfunction "1_1") (pintype "passive"))
    )
    (net (code "37") (name "Net-(D3-D)") (class "Default")
      (node (ref "D3") (pin "5") (pinfunction "D_5") (pintype "passive"))
      (node (ref "R19") (pin "1") (pinfunction "1_1") (pintype "passive"))
    )
    (net (code "38") (name "Net-(D3-DP)") (class "Default")
      (node (ref "D3") (pin "6") (pinfunction "DP_6") (pintype "passive"))
      (node (ref "R17") (pin "2") (pinfunction "2_2") (pintype "passive"))
    )
    (net (code "39") (name "Net-(D3-E)") (class "Default")
      (node (ref "D3") (pin "4") (pinfunction "E_4") (pintype "passive"))
      (node (ref "R20") (pin "1") (pinfunction "1_1") (pintype "passive"))
    )
    (net (code "40") (name "Net-(D3-F)") (class "Default")
      (node (ref "D3") (pin "2") (pinfunction "F_2") (pintype "passive"))
      (node (ref "R9") (pin "2") (pinfunction "2_2") (pintype "passive"))
    )
    (net (code "41") (name "Net-(D3-G)") (class "Default")
      (node (ref "D3") (pin "1") (pinfunction "G_1") (pintype "passive"))
      (node (ref "R14") (pin "2") (pinfunction "2_2") (pintype "passive"))
    )
    (net (code "42") (name "Net-(D7-A)") (class "Default")
      (node (ref "D7") (pin "10") (pinfunction "A_10") (pintype "passive"))
      (node (ref "R22") (pin "1") (pinfunction "1_1") (pintype "passive"))
    )
    (net (code "43") (name "Net-(D7-B)") (class "Default")
      (node (ref "D7") (pin "9") (pinfunction "B_9") (pintype "passive"))
      (node (ref "R27") (pin "1") (pinfunction "1_1") (pintype "passive"))
    )
    (net (code "44") (name "Net-(D7-C)") (class "Default")
      (node (ref "D7") (pin "7") (pinfunction "C_7") (pintype "passive"))
      (node (ref "R29") (pin "1") (pinfunction "1_1") (pintype "passive"))
    )
    (net (code "45") (name "Net-(D7-D)") (class "Default")
      (node (ref "D7") (pin "5") (pinfunction "D_5") (pintype "passive"))
      (node (ref "R30") (pin "1") (pinfunction "1_1") (pintype "passive"))
    )
    (net (code "46") (name "Net-(D7-DP)") (class "Default")
      (node (ref "D7") (pin "6") (pinfunction "DP_6") (pintype "passive"))
      (node (ref "R28") (pin "2") (pinfunction "2_2") (pintype "passive"))
    )
    (net (code "47") (name "Net-(D7-E)") (class "Default")
      (node (ref "D7") (pin "4") (pinfunction "E_4") (pintype "passive"))
      (node (ref "R31") (pin "1") (pinfunction "1_1") (pintype "passive"))
    )
    (net (code "48") (name "Net-(D7-F)") (class "Default")
      (node (ref "D7") (pin "2") (pinfunction "F_2") (pintype "passive"))
      (node (ref "R21") (pin "2") (pinfunction "2_2") (pintype "passive"))
    )
    (net (code "49") (name "Net-(D7-G)") (class "Default")
      (node (ref "D7") (pin "1") (pinfunction "G_1") (pintype "passive"))
      (node (ref "R25") (pin "2") (pinfunction "2_2") (pintype "passive"))
    )
    (net (code "50") (name "Net-(D8-A)") (class "Default")
      (node (ref "D8") (pin "10") (pinfunction "A_10") (pintype "passive"))
      (node (ref "R33") (pin "1") (pinfunction "1_1") (pintype "passive"))
    )
    (net (code "51") (name "Net-(D8-B)") (class "Default")
      (node (ref "D8") (pin "9") (pinfunction "B_9") (pintype "passive"))
      (node (ref "R35") (pin "1") (pinfunction "1_1") (pintype "passive"))
    )
    (net (code "52") (name "Net-(D8-C)") (class "Default")
      (node (ref "D8") (pin "7") (pinfunction "C_7") (pintype "passive"))
      (node (ref "R37") (pin "1") (pinfunction "1_1") (pintype "passive"))
    )
    (net (code "53") (name "Net-(D8-D)") (class "Default")
      (node (ref "D8") (pin "5") (pinfunction "D_5") (pintype "passive"))
      (node (ref "R38") (pin "1") (pinfunction "1_1") (pintype "passive"))
    )
    (net (code "54") (name "Net-(D8-DP)") (class "Default")
      (node (ref "D8") (pin "6") (pinfunction "DP_6") (pintype "passive"))
      (node (ref "R36") (pin "2") (pinfunction "2_2") (pintype "passive"))
    )
    (net (code "55") (name "Net-(D8-E)") (class "Default")
      (node (ref "D8") (pin "4") (pinfunction "E_4") (pintype "passive"))
      (node (ref "R39") (pin "1") (pinfunction "1_1") (pintype "passive"))
    )
    (net (code "56") (name "Net-(D8-F)") (class "Default")
      (node (ref "D8") (pin "2") (pinfunction "F_2") (pintype "passive"))
      (node (ref "R32") (pin "2") (pinfunction "2_2") (pintype "passive"))
    )
    (net (code "57") (name "Net-(D8-G)") (class "Default")
      (node (ref "D8") (pin "1") (pinfunction "G_1") (pintype "passive"))
      (node (ref "R34") (pin "2") (pinfunction "2_2") (pintype "passive"))
    )
    (net (code "58") (name "Net-(D9-A)") (class "Default")
      (node (ref "D9") (pin "2") (pinfunction "A_2") (pintype "passive"))
      (node (ref "R10") (pin "1") (pinfunction "1_1") (pintype "passive"))
    )
    (net (code "59") (name "Net-(D10-PadA)") (class "Default")
      (node (ref "D10") (pin "A") (pinfunction "A_A") (pintype "passive"))
      (node (ref "R2") (pin "1") (pinfunction "1_1") (pintype "passive"))
    )
    (net (code "60") (name "Net-(IC1A-PB2)") (class "Default")
      (node (ref "IC1") (pin "20") (pinfunction "PB2_20") (pintype "passive"))
      (node (ref "R26") (pin "1") (pinfunction "1_1") (pintype "passive"))
    )
    (net (code "61") (name "Net-(IC1A-PB3)") (class "Default")
      (node (ref "IC1") (pin "39") (pinfunction "PB3_39") (pintype "passive"))
      (node (ref "R62") (pin "1") (pinfunction "1_1") (pintype "passive"))
    )
    (net (code "62") (name "Net-(IC1A-PB4)") (class "Default")
      (node (ref "IC1") (pin "40") (pinfunction "PB4_40") (pintype "passive"))
      (node (ref "R68") (pin "1") (pinfunction "1_1") (pintype "passive"))
    )
    (net (code "63") (name "Net-(IC1A-PB14)") (class "Default")
      (node (ref "IC1") (pin "27") (pinfunction "PB14_27") (pintype "passive"))
      (node (ref "R61") (pin "1") (pinfunction "1_1") (pintype "passive"))
    )
    (net (code "64") (name "Net-(IC1A-PB15)") (class "Default")
      (node (ref "IC1") (pin "28") (pinfunction "PB15_28") (pintype "passive"))
      (node (ref "R82") (pin "1") (pinfunction "1_1") (pintype "passive"))
    )
    (net (code "65") (name "Net-(IC1A-PD0-OSC_IN)") (class "Default")
      (node (ref "C6") (pin "1") (pinfunction "1_1") (pintype "passive"))
      (node (ref "IC1") (pin "5") (pinfunction "PD0-OSC_IN_5") (pintype "passive"))
      (node (ref "Y1") (pin "1") (pinfunction "OSC1_1") (pintype "passive"))
    )
    (net (code "66") (name "Net-(IC1A-PD1)") (class "Default")
      (node (ref "C10") (pin "1") (pinfunction "1_1") (pintype "passive"))
      (node (ref "IC1") (pin "6") (pinfunction "PD1_6") (pintype "passive"))
      (node (ref "Y1") (pin "2") (pinfunction "OSC2_2") (pintype "passive"))
    )
    (net (code "67") (name "Net-(IC2-OutA)") (class "Default")
      (node (ref "IC2") (pin "15") (pinfunction "OutA_15") (pintype "passive"))
      (node (ref "R11") (pin "2") (pinfunction "2_2") (pintype "passive"))
    )
    (net (code "68") (name "Net-(IC2-OutB)") (class "Default")
      (node (ref "IC2") (pin "1") (pinfunction "OutB_1") (pintype "passive"))
      (node (ref "R15") (pin "2") (pinfunction "2_2") (pintype "passive"))
    )
    (net (code "69") (name "Net-(IC2-OutC)") (class "Default")
      (node (ref "IC2") (pin "2") (pinfunction "OutC_2") (pintype "passive"))
      (node (ref "R18") (pin "2") (pinfunction "2_2") (pintype "passive"))
    )
    (net (code "70") (name "Net-(IC2-OutD)") (class "Default")
      (node (ref "IC2") (pin "3") (pinfunction "OutD_3") (pintype "passive"))
      (node (ref "R19") (pin "2") (pinfunction "2_2") (pintype "passive"))
    )
    (net (code "71") (name "Net-(IC2-OutE)") (class "Default")
      (node (ref "IC2") (pin "4") (pinfunction "OutE_4") (pintype "passive"))
      (node (ref "R20") (pin "2") (pinfunction "2_2") (pintype "passive"))
    )
    (net (code "72") (name "Net-(IC2-OutF)") (class "Default")
      (node (ref "IC2") (pin "5") (pinfunction "OutF_5") (pintype "passive"))
      (node (ref "R9") (pin "1") (pinfunction "1_1") (pintype "passive"))
    )
    (net (code "73") (name "Net-(IC2-OutG)") (class "Default")
      (node (ref "IC2") (pin "6") (pinfunction "OutG_6") (pintype "passive"))
      (node (ref "R14") (pin "1") (pinfunction "1_1") (pintype "passive"))
    )
    (net (code "74") (name "Net-(IC2-OutH)") (class "Default")
      (node (ref "IC2") (pin "7") (pinfunction "OutH_7") (pintype "passive"))
      (node (ref "R17") (pin "1") (pinfunction "1_1") (pintype "passive"))
    )
    (net (code "75") (name "Net-(IC3-OutA)") (class "Default")
      (node (ref "IC3") (pin "15") (pinfunction "OutA_15") (pintype "passive"))
      (node (ref "R22") (pin "2") (pinfunction "2_2") (pintype "passive"))
    )
    (net (code "76") (name "Net-(IC3-OutB)") (class "Default")
      (node (ref "IC3") (pin "1") (pinfunction "OutB_1") (pintype "passive"))
      (node (ref "R27") (pin "2") (pinfunction "2_2") (pintype "passive"))
    )
    (net (code "77") (name "Net-(IC3-OutC)") (class "Default")
      (node (ref "IC3") (pin "2") (pinfunction "OutC_2") (pintype "passive"))
      (node (ref "R29") (pin "2") (pinfunction "2_2") (pintype "passive"))
    )
    (net (code "78") (name "Net-(IC3-OutD)") (class "Default")
      (node (ref "IC3") (pin "3") (pinfunction "OutD_3") (pintype "passive"))
      (node (ref "R30") (pin "2") (pinfunction "2_2") (pintype "passive"))
    )
    (net (code "79") (name "Net-(IC3-OutE)") (class "Default")
      (node (ref "IC3") (pin "4") (pinfunction "OutE_4") (pintype "passive"))
      (node (ref "R31") (pin "2") (pinfunction "2_2") (pintype "passive"))
    )
    (net (code "80") (name "Net-(IC3-OutF)") (class "Default")
      (node (ref "IC3") (pin "5") (pinfunction "OutF_5") (pintype "passive"))
      (node (ref "R21") (pin "1") (pinfunction "1_1") (pintype "passive"))
    )
    (net (code "81") (name "Net-(IC3-OutG)") (class "Default")
      (node (ref "IC3") (pin "6") (pinfunction "OutG_6") (pintype "passive"))
      (node (ref "R25") (pin "1") (pinfunction "1_1") (pintype "passive"))
    )
    (net (code "82") (name "Net-(IC3-OutH)") (class "Default")
      (node (ref "IC3") (pin "7") (pinfunction "OutH_7") (pintype "passive"))
      (node (ref "R28") (pin "1") (pinfunction "1_1") (pintype "passive"))
    )
    (net (code "83") (name "Net-(IC4-OutA)") (class "Default")
      (node (ref "IC4") (pin "15") (pinfunction "OutA_15") (pintype "passive"))
      (node (ref "R33") (pin "2") (pinfunction "2_2") (pintype "passive"))
    )
    (net (code "84") (name "Net-(IC4-OutB)") (class "Default")
      (node (ref "IC4") (pin "1") (pinfunction "OutB_1") (pintype "passive"))
      (node (ref "R35") (pin "2") (pinfunction "2_2") (pintype "passive"))
    )
    (net (code "85") (name "Net-(IC4-OutC)") (class "Default")
      (node (ref "IC4") (pin "2") (pinfunction "OutC_2") (pintype "passive"))
      (node (ref "R37") (pin "2") (pinfunction "2_2") (pintype "passive"))
    )
    (net (code "86") (name "Net-(IC4-OutD)") (class "Default")
      (node (ref "IC4") (pin "3") (pinfunction "OutD_3") (pintype "passive"))
      (node (ref "R38") (pin "2") (pinfunction "2_2") (pintype "passive"))
    )
    (net (code "87") (name "Net-(IC4-OutE)") (class "Default")
      (node (ref "IC4") (pin "4") (pinfunction "OutE_4") (pintype "passive"))
      (node (ref "R39") (pin "2") (pinfunction "2_2") (pintype "passive"))
    )
    (net (code "88") (name "Net-(IC4-OutF)") (class "Default")
      (node (ref "IC4") (pin "5") (pinfunction "OutF_5") (pintype "passive"))
      (node (ref "R32") (pin "1") (pinfunction "1_1") (pintype "passive"))
    )
    (net (code "89") (name "Net-(IC4-OutG)") (class "Default")
      (node (ref "IC4") (pin "6") (pinfunction "OutG_6") (pintype "passive"))
      (node (ref "R34") (pin "1") (pinfunction "1_1") (pintype "passive"))
    )
    (net (code "90") (name "Net-(IC4-OutH)") (class "Default")
      (node (ref "IC4") (pin "7") (pinfunction "OutH_7") (pintype "passive"))
      (node (ref "R36") (pin "1") (pinfunction "1_1") (pintype "passive"))
    )
    (net (code "91") (name "unconnected-(IC1A-PA0-WKUP-Pad10)") (class "Default")
      (node (ref "IC1") (pin "10") (pinfunction "PA0-WKUP_10") (pintype "passive+no_connect"))
    )
    (net (code "92") (name "unconnected-(IC1A-PA1-Pad11)") (class "Default")
      (node (ref "IC1") (pin "11") (pinfunction "PA1_11") (pintype "passive+no_connect"))
    )
    (net (code "93") (name "unconnected-(IC1A-PA8-Pad29)") (class "Default")
      (node (ref "IC1") (pin "29") (pinfunction "PA8_29") (pintype "passive+no_connect"))
    )
    (net (code "94") (name "unconnected-(IC1A-PA11-Pad32)") (class "Default")
      (node (ref "IC1") (pin "32") (pinfunction "PA11_32") (pintype "passive+no_connect"))
    )
    (net (code "95") (name "unconnected-(IC1A-PA12-Pad33)") (class "Default")
      (node (ref "IC1") (pin "33") (pinfunction "PA12_33") (pintype "passive+no_connect"))
    )
    (net (code "96") (name "unconnected-(IC1A-PA15-Pad38)") (class "Default")
      (node (ref "IC1") (pin "38") (pinfunction "PA15_38") (pintype "passive"))
    )
    (net (code "97") (name "unconnected-(IC1A-PB0-Pad18)") (class "Default")
      (node (ref "IC1") (pin "18") (pinfunction "PB0_18") (pintype "passive+no_connect"))
    )
    (net (code "98") (name "unconnected-(IC1A-PB1-Pad19)") (class "Default")
      (node (ref "IC1") (pin "19") (pinfunction "PB1_19") (pintype "passive+no_connect"))
    )
    (net (code "99") (name "unconnected-(IC1A-PC13-TAMPER-RTC-Pad2)") (class "Default")
      (node (ref "IC1") (pin "2") (pinfunction "PC13-TAMPER-RTC_2") (pintype "passive+no_connect"))
    )
    (net (code "100") (name "unconnected-(IC1A-PC14-OSC32_IN-Pad3)") (class "Default")
      (node (ref "IC1") (pin "3") (pinfunction "PC14-OSC32_IN_3") (pintype "passive+no_connect"))
    )
    (net (code "101") (name "unconnected-(IC1A-PC15-OSC32_OUT-Pad4)") (class "Default")
      (node (ref "IC1") (pin "4") (pinfunction "PC15-OSC32_OUT_4") (pintype "passive+no_connect"))
    )
    (net (code "102") (name "unconnected-(R26-Pad2)") (class "Default")
      (node (ref "R26") (pin "2") (pinfunction "2_2") (pintype "passive+no_connect"))
    )
  )
)
